# Resolver.net
KiCad netlist of a schematic drawn in Altium Designer
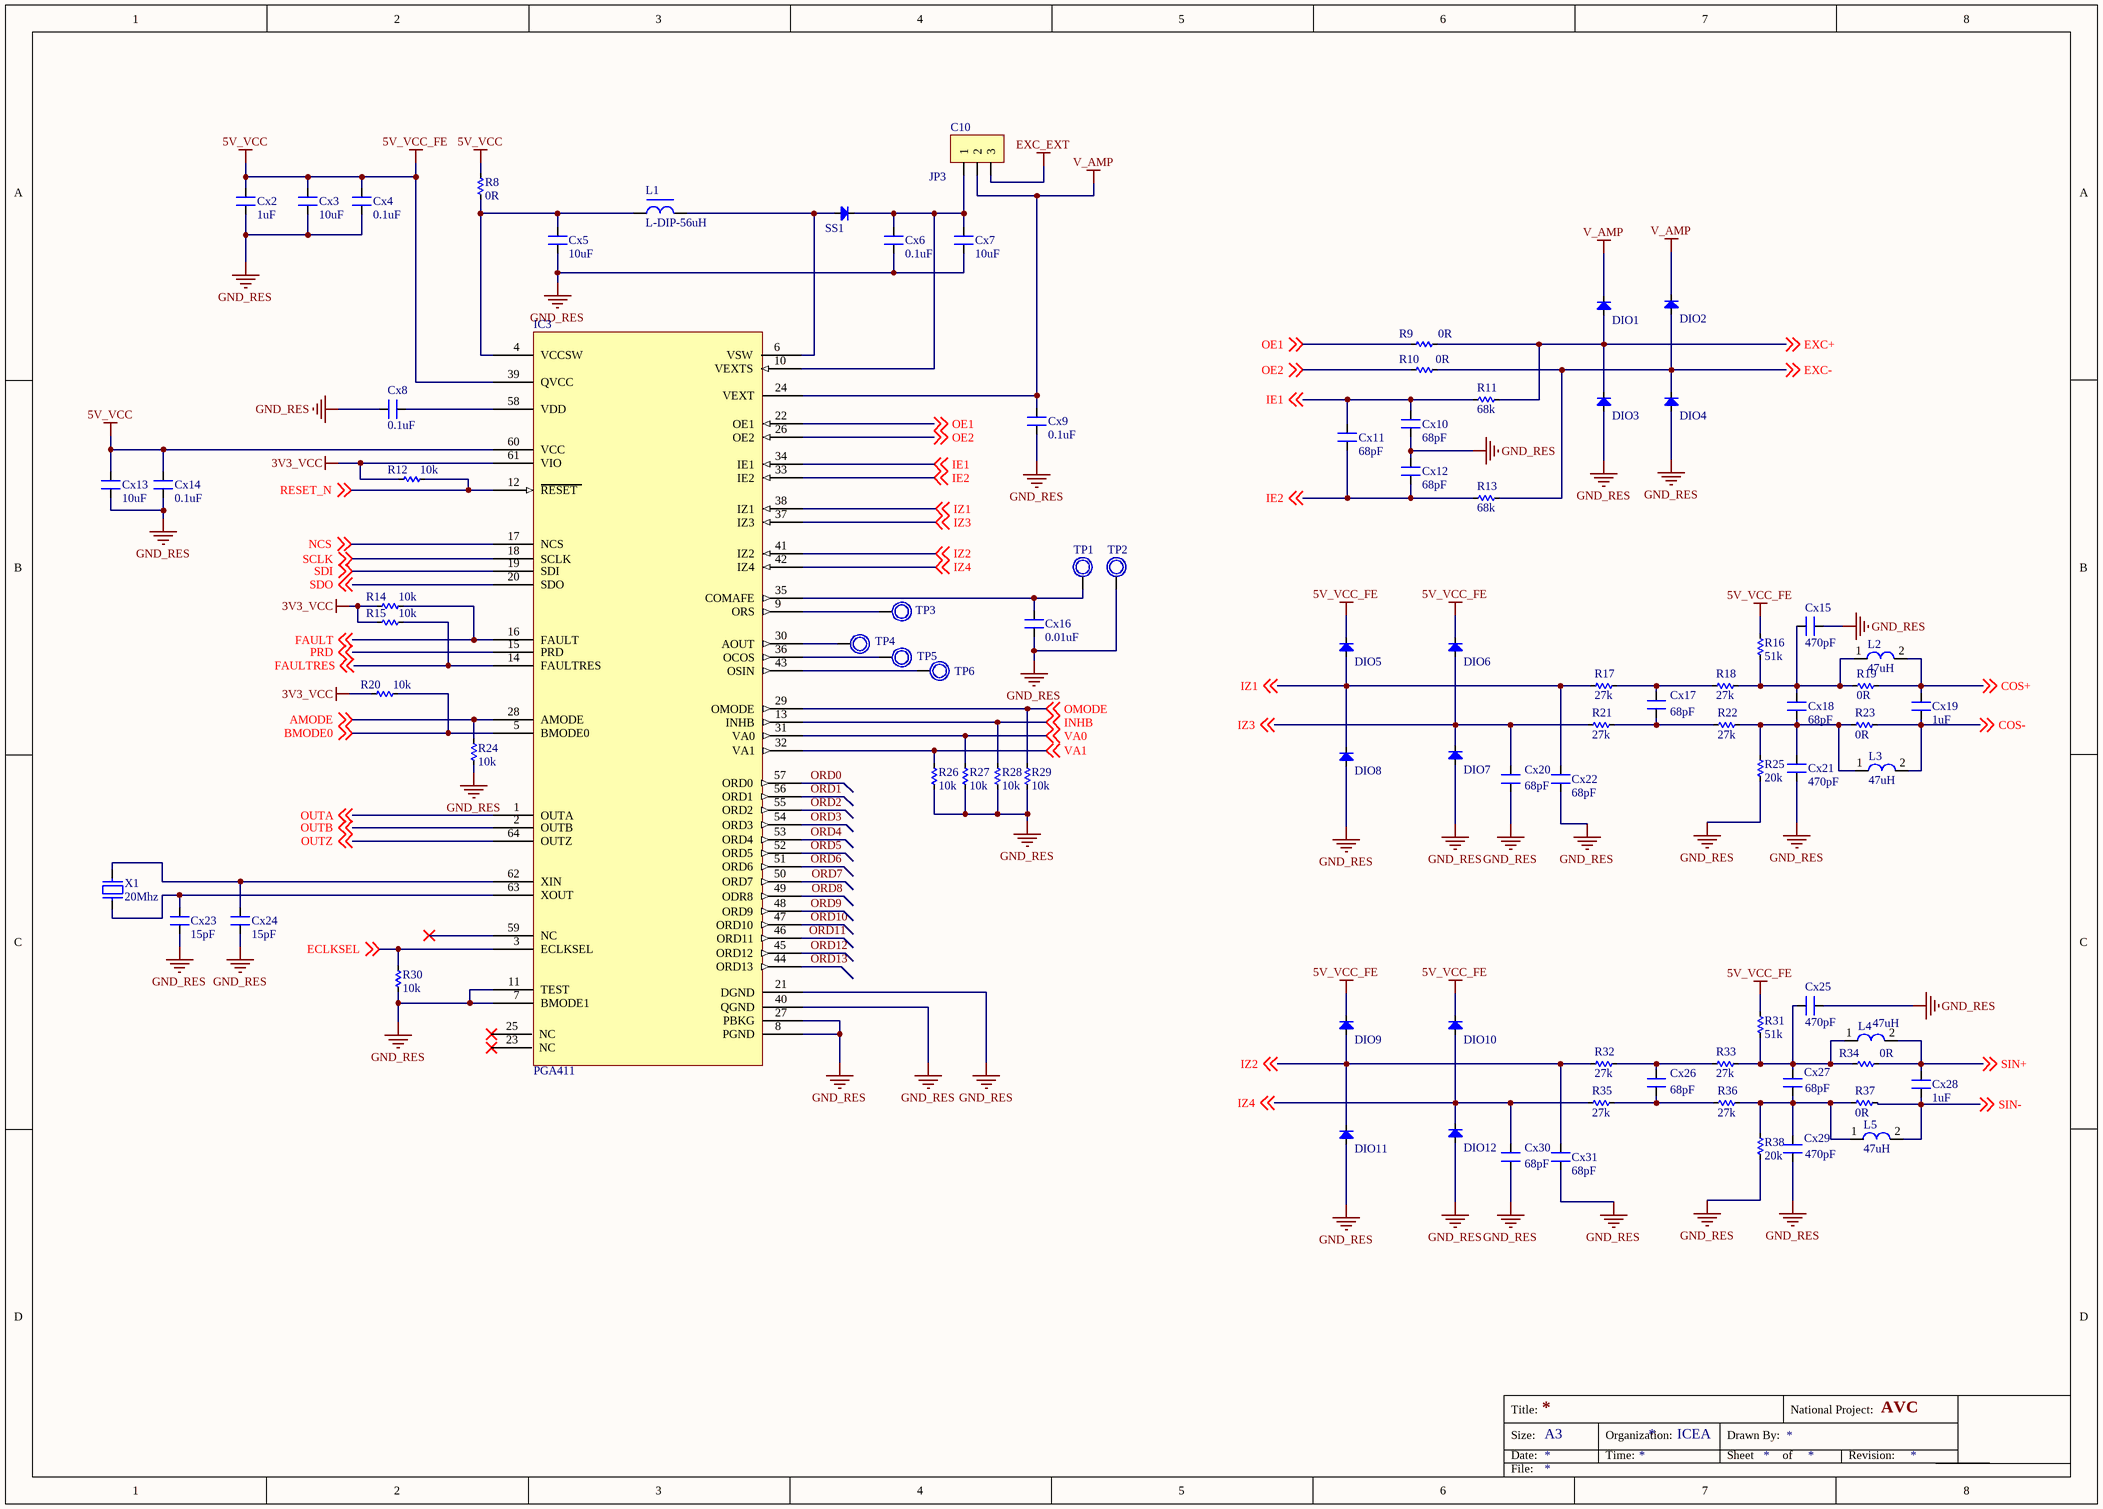
[diagram p0: Resolver.SchDoc]

(export (version "E")
  (design (tool "Eeschema 10.0.6"))
  (components
    (comp (ref "C10")
      (value "JP3")
      (footprint "JP3-CLOSED")
      (description "WR-PHD 2.54 mm Angled Socket Header")
      (fields
        (field (name "MANUFACTURER") "Würth Elektronik eiSos GmbH")
        (field (name "PARTNO") "613003143121")
        (field (name "CREATED BY") "Karrer Zheng")
      )
      (libsource (lib "ImetAltiumLibrary") (part "JP3"))
    )
    (comp (ref "Cx2")
      (value "1uF")
      (footprint "CN-SMD-0805")
      (libsource (lib "ImetAltiumLibrary") (part "CN"))
    )
    (comp (ref "Cx3")
      (value "10uF")
      (footprint "CN-SMD-1206")
      (libsource (lib "ImetAltiumLibrary") (part "CN"))
    )
    (comp (ref "Cx4")
      (value "0.1uF")
      (footprint "CN-SMD-0805")
      (libsource (lib "ImetAltiumLibrary") (part "CN"))
    )
    (comp (ref "Cx5")
      (value "10uF")
      (footprint "CN-SMD-1206")
      (libsource (lib "ImetAltiumLibrary") (part "CN"))
    )
    (comp (ref "Cx6")
      (value "0.1uF")
      (footprint "CN-SMD-0805")
      (libsource (lib "ImetAltiumLibrary") (part "CN"))
    )
    (comp (ref "Cx7")
      (value "10uF")
      (footprint "CN-SMD-1206")
      (libsource (lib "ImetAltiumLibrary") (part "CN"))
    )
    (comp (ref "Cx8")
      (value "0.1uF")
      (footprint "CN-SMD-0805")
      (libsource (lib "ImetAltiumLibrary") (part "CN"))
    )
    (comp (ref "Cx9")
      (value "0.1uF")
      (footprint "CN-SMD-0805")
      (libsource (lib "ImetAltiumLibrary") (part "CN"))
    )
    (comp (ref "Cx10")
      (value "68pF")
      (footprint "CN-SMD-0805")
      (libsource (lib "ImetAltiumLibrary") (part "CN"))
    )
    (comp (ref "Cx11")
      (value "68pF")
      (footprint "CN-SMD-0805")
      (libsource (lib "ImetAltiumLibrary") (part "CN"))
    )
    (comp (ref "Cx12")
      (value "68pF")
      (footprint "CN-SMD-0805")
      (libsource (lib "ImetAltiumLibrary") (part "CN"))
    )
    (comp (ref "Cx13")
      (value "10uF")
      (footprint "CN-SMD-1206")
      (libsource (lib "ImetAltiumLibrary") (part "CN"))
    )
    (comp (ref "Cx14")
      (value "0.1uF")
      (footprint "CN-SMD-0805")
      (libsource (lib "ImetAltiumLibrary") (part "CN"))
    )
    (comp (ref "Cx15")
      (value "470pF")
      (footprint "CN-SMD-0805")
      (libsource (lib "ImetAltiumLibrary") (part "CN"))
    )
    (comp (ref "Cx16")
      (value "0.01uF")
      (footprint "CN-SMD-0805")
      (libsource (lib "ImetAltiumLibrary") (part "CN"))
    )
    (comp (ref "Cx17")
      (value "68pF")
      (footprint "CN-SMD-0805")
      (libsource (lib "ImetAltiumLibrary") (part "CN"))
    )
    (comp (ref "Cx18")
      (value "68pF")
      (footprint "CN-SMD-0805")
      (libsource (lib "ImetAltiumLibrary") (part "CN"))
    )
    (comp (ref "Cx19")
      (value "1uF")
      (footprint "CN-SMD-0805")
      (libsource (lib "ImetAltiumLibrary") (part "CN"))
    )
    (comp (ref "Cx20")
      (value "68pF")
      (footprint "CN-SMD-0805")
      (libsource (lib "ImetAltiumLibrary") (part "CN"))
    )
    (comp (ref "Cx21")
      (value "470pF")
      (footprint "CN-SMD-0805")
      (libsource (lib "ImetAltiumLibrary") (part "CN"))
    )
    (comp (ref "Cx22")
      (value "68pF")
      (footprint "CN-SMD-0805")
      (libsource (lib "ImetAltiumLibrary") (part "CN"))
    )
    (comp (ref "Cx23")
      (value "15pF")
      (footprint "CN-SMD-0805")
      (libsource (lib "ImetAltiumLibrary") (part "CN"))
    )
    (comp (ref "Cx24")
      (value "15pF")
      (footprint "CN-SMD-0805")
      (libsource (lib "ImetAltiumLibrary") (part "CN"))
    )
    (comp (ref "Cx25")
      (value "470pF")
      (footprint "CN-SMD-0805")
      (libsource (lib "ImetAltiumLibrary") (part "CN"))
    )
    (comp (ref "Cx26")
      (value "68pF")
      (footprint "CN-SMD-0805")
      (libsource (lib "ImetAltiumLibrary") (part "CN"))
    )
    (comp (ref "Cx27")
      (value "68pF")
      (footprint "CN-SMD-0805")
      (libsource (lib "ImetAltiumLibrary") (part "CN"))
    )
    (comp (ref "Cx28")
      (value "1uF")
      (footprint "CN-SMD-0805")
      (libsource (lib "ImetAltiumLibrary") (part "CN"))
    )
    (comp (ref "Cx29")
      (value "470pF")
      (footprint "CN-SMD-0805")
      (libsource (lib "ImetAltiumLibrary") (part "CN"))
    )
    (comp (ref "Cx30")
      (value "68pF")
      (footprint "CN-SMD-0805")
      (libsource (lib "ImetAltiumLibrary") (part "CN"))
    )
    (comp (ref "Cx31")
      (value "68pF")
      (footprint "CN-SMD-0805")
      (libsource (lib "ImetAltiumLibrary") (part "CN"))
    )
    (comp (ref "DIO1")
      (value "Diode SMD")
      (footprint "DIO-SMD-106")
      (description "Default Diode")
      (fields (field (name "PUBLISHER") "Altium Limited"))
      (libsource (lib "ImetAltiumLibrary") (part "Diode SMD"))
    )
    (comp (ref "DIO2")
      (value "Diode SMD")
      (footprint "DIO-SMD-106")
      (description "Default Diode")
      (fields (field (name "PUBLISHER") "Altium Limited"))
      (libsource (lib "ImetAltiumLibrary") (part "Diode SMD"))
    )
    (comp (ref "DIO3")
      (value "Diode SMD")
      (footprint "DIO-SMD-106")
      (description "Default Diode")
      (fields (field (name "PUBLISHER") "Altium Limited"))
      (libsource (lib "ImetAltiumLibrary") (part "Diode SMD"))
    )
    (comp (ref "DIO4")
      (value "Diode SMD")
      (footprint "DIO-SMD-106")
      (description "Default Diode")
      (fields (field (name "PUBLISHER") "Altium Limited"))
      (libsource (lib "ImetAltiumLibrary") (part "Diode SMD"))
    )
    (comp (ref "DIO5")
      (value "Diode SMD")
      (footprint "DIO-SMD-106")
      (description "Default Diode")
      (fields (field (name "PUBLISHER") "Altium Limited"))
      (libsource (lib "ImetAltiumLibrary") (part "Diode SMD"))
    )
    (comp (ref "DIO6")
      (value "Diode SMD")
      (footprint "DIO-SMD-106")
      (description "Default Diode")
      (fields (field (name "PUBLISHER") "Altium Limited"))
      (libsource (lib "ImetAltiumLibrary") (part "Diode SMD"))
    )
    (comp (ref "DIO7")
      (value "Diode SMD")
      (footprint "DIO-SMD-106")
      (description "Default Diode")
      (fields (field (name "PUBLISHER") "Altium Limited"))
      (libsource (lib "ImetAltiumLibrary") (part "Diode SMD"))
    )
    (comp (ref "DIO8")
      (value "Diode SMD")
      (footprint "DIO-SMD-106")
      (description "Default Diode")
      (fields (field (name "PUBLISHER") "Altium Limited"))
      (libsource (lib "ImetAltiumLibrary") (part "Diode SMD"))
    )
    (comp (ref "DIO9")
      (value "Diode SMD")
      (footprint "DIO-SMD-106")
      (description "Default Diode")
      (fields (field (name "PUBLISHER") "Altium Limited"))
      (libsource (lib "ImetAltiumLibrary") (part "Diode SMD"))
    )
    (comp (ref "DIO10")
      (value "Diode SMD")
      (footprint "DIO-SMD-106")
      (description "Default Diode")
      (fields (field (name "PUBLISHER") "Altium Limited"))
      (libsource (lib "ImetAltiumLibrary") (part "Diode SMD"))
    )
    (comp (ref "DIO11")
      (value "Diode SMD")
      (footprint "DIO-SMD-106")
      (description "Default Diode")
      (fields (field (name "PUBLISHER") "Altium Limited"))
      (libsource (lib "ImetAltiumLibrary") (part "Diode SMD"))
    )
    (comp (ref "DIO12")
      (value "Diode SMD")
      (footprint "DIO-SMD-106")
      (description "Default Diode")
      (fields (field (name "PUBLISHER") "Altium Limited"))
      (libsource (lib "ImetAltiumLibrary") (part "Diode SMD"))
    )
    (comp (ref "IC3") (value "PGA411") (footprint "PGA411") (libsource (lib "PELAB") (part "PGA411")))
    (comp (ref "L1")
      (value "L-DIP-56uH")
      (footprint "L-DIP-M-13.5x6")
      (description "Inductor")
      (libsource (lib "ImetAltiumLibrary") (part "L-DIP-1"))
    )
    (comp (ref "L2")
      (value "47uH")
      (footprint "L CD43")
      (fields
        (field (name "PARTNO") "78477010")
        (field (name "MANUFACTURER") "Wurth Elektronik")
        (field (name "CREATED BY") "Baojun Chen")
      )
      (libsource (lib "ImetAltiumLibrary") (part "L-SMD-1"))
    )
    (comp (ref "L3")
      (value "47uH")
      (footprint "L CD43")
      (fields
        (field (name "PARTNO") "78477010")
        (field (name "MANUFACTURER") "Wurth Elektronik")
        (field (name "CREATED BY") "Baojun Chen")
      )
      (libsource (lib "ImetAltiumLibrary") (part "L-SMD-1"))
    )
    (comp (ref "L4")
      (value "47uH")
      (footprint "L CD43")
      (fields
        (field (name "PARTNO") "78477010")
        (field (name "MANUFACTURER") "Wurth Elektronik")
        (field (name "CREATED BY") "Baojun Chen")
      )
      (libsource (lib "ImetAltiumLibrary") (part "L-SMD-1"))
    )
    (comp (ref "L5")
      (value "47uH")
      (footprint "L CD43")
      (fields
        (field (name "PARTNO") "78477010")
        (field (name "MANUFACTURER") "Wurth Elektronik")
        (field (name "CREATED BY") "Baojun Chen")
      )
      (libsource (lib "ImetAltiumLibrary") (part "L-SMD-1"))
    )
    (comp (ref "R8")
      (value "0R")
      (footprint "RES-SMD-0805")
      (description "Resistor")
      (fields
        (field (name "MANUFACTURER") "Generic Components")
        (field (name "PUBLISHER") "Altium Hobart Technology Centre")
      )
      (libsource (lib "ImetAltiumLibrary") (part "Res-SMD"))
    )
    (comp (ref "R9")
      (value "0R")
      (footprint "RES-SMD-0805")
      (description "Resistor")
      (fields
        (field (name "MANUFACTURER") "Generic Components")
        (field (name "PUBLISHER") "Altium Hobart Technology Centre")
      )
      (libsource (lib "ImetAltiumLibrary") (part "Res-SMD"))
    )
    (comp (ref "R10")
      (value "0R")
      (footprint "RES-SMD-0805")
      (description "Resistor")
      (fields
        (field (name "MANUFACTURER") "Generic Components")
        (field (name "PUBLISHER") "Altium Hobart Technology Centre")
      )
      (libsource (lib "ImetAltiumLibrary") (part "Res-SMD"))
    )
    (comp (ref "R11")
      (value "68k")
      (footprint "RES-SMD-0805")
      (description "Resistor")
      (fields
        (field (name "MANUFACTURER") "Generic Components")
        (field (name "PUBLISHER") "Altium Hobart Technology Centre")
      )
      (libsource (lib "ImetAltiumLibrary") (part "Res-SMD"))
    )
    (comp (ref "R12")
      (value "10k")
      (footprint "RES-SMD-0805")
      (description "Resistor")
      (fields
        (field (name "MANUFACTURER") "Generic Components")
        (field (name "PUBLISHER") "Altium Hobart Technology Centre")
      )
      (libsource (lib "ImetAltiumLibrary") (part "Res-SMD"))
    )
    (comp (ref "R13")
      (value "68k")
      (footprint "RES-SMD-0805")
      (description "Resistor")
      (fields
        (field (name "MANUFACTURER") "Generic Components")
        (field (name "PUBLISHER") "Altium Hobart Technology Centre")
      )
      (libsource (lib "ImetAltiumLibrary") (part "Res-SMD"))
    )
    (comp (ref "R14")
      (value "10k")
      (footprint "RES-SMD-0805")
      (description "Resistor")
      (fields
        (field (name "MANUFACTURER") "Generic Components")
        (field (name "PUBLISHER") "Altium Hobart Technology Centre")
      )
      (libsource (lib "ImetAltiumLibrary") (part "Res-SMD"))
    )
    (comp (ref "R15")
      (value "10k")
      (footprint "RES-SMD-0805")
      (description "Resistor")
      (fields
        (field (name "MANUFACTURER") "Generic Components")
        (field (name "PUBLISHER") "Altium Hobart Technology Centre")
      )
      (libsource (lib "ImetAltiumLibrary") (part "Res-SMD"))
    )
    (comp (ref "R16")
      (value "51k")
      (footprint "RES-SMD-0805")
      (description "Resistor")
      (fields
        (field (name "MANUFACTURER") "Generic Components")
        (field (name "PUBLISHER") "Altium Hobart Technology Centre")
      )
      (libsource (lib "ImetAltiumLibrary") (part "Res-SMD"))
    )
    (comp (ref "R17")
      (value "27k")
      (footprint "RES-SMD-0805")
      (description "Resistor")
      (fields
        (field (name "MANUFACTURER") "Generic Components")
        (field (name "PUBLISHER") "Altium Hobart Technology Centre")
      )
      (libsource (lib "ImetAltiumLibrary") (part "Res-SMD"))
    )
    (comp (ref "R18")
      (value "27k")
      (footprint "RES-SMD-0805")
      (description "Resistor")
      (fields
        (field (name "MANUFACTURER") "Generic Components")
        (field (name "PUBLISHER") "Altium Hobart Technology Centre")
      )
      (libsource (lib "ImetAltiumLibrary") (part "Res-SMD"))
    )
    (comp (ref "R19")
      (value "0R")
      (footprint "RES-SMD-0805")
      (description "Resistor")
      (fields
        (field (name "MANUFACTURER") "Generic Components")
        (field (name "PUBLISHER") "Altium Hobart Technology Centre")
      )
      (libsource (lib "ImetAltiumLibrary") (part "Res-SMD"))
    )
    (comp (ref "R20")
      (value "10k")
      (footprint "RES-SMD-0805")
      (description "Resistor")
      (fields
        (field (name "MANUFACTURER") "Generic Components")
        (field (name "PUBLISHER") "Altium Hobart Technology Centre")
      )
      (libsource (lib "ImetAltiumLibrary") (part "Res-SMD"))
    )
    (comp (ref "R21")
      (value "27k")
      (footprint "RES-SMD-0805")
      (description "Resistor")
      (fields
        (field (name "MANUFACTURER") "Generic Components")
        (field (name "PUBLISHER") "Altium Hobart Technology Centre")
      )
      (libsource (lib "ImetAltiumLibrary") (part "Res-SMD"))
    )
    (comp (ref "R22")
      (value "27k")
      (footprint "RES-SMD-0805")
      (description "Resistor")
      (fields
        (field (name "MANUFACTURER") "Generic Components")
        (field (name "PUBLISHER") "Altium Hobart Technology Centre")
      )
      (libsource (lib "ImetAltiumLibrary") (part "Res-SMD"))
    )
    (comp (ref "R23")
      (value "0R")
      (footprint "RES-SMD-0805")
      (description "Resistor")
      (fields
        (field (name "MANUFACTURER") "Generic Components")
        (field (name "PUBLISHER") "Altium Hobart Technology Centre")
      )
      (libsource (lib "ImetAltiumLibrary") (part "Res-SMD"))
    )
    (comp (ref "R24")
      (value "10k")
      (footprint "RES-SMD-0805")
      (description "Resistor")
      (fields
        (field (name "MANUFACTURER") "Generic Components")
        (field (name "PUBLISHER") "Altium Hobart Technology Centre")
      )
      (libsource (lib "ImetAltiumLibrary") (part "Res-SMD"))
    )
    (comp (ref "R25")
      (value "20k")
      (footprint "RES-SMD-0805")
      (description "Resistor")
      (fields
        (field (name "MANUFACTURER") "Generic Components")
        (field (name "PUBLISHER") "Altium Hobart Technology Centre")
      )
      (libsource (lib "ImetAltiumLibrary") (part "Res-SMD"))
    )
    (comp (ref "R26")
      (value "10k")
      (footprint "RES-SMD-0805")
      (description "Resistor")
      (fields
        (field (name "MANUFACTURER") "Generic Components")
        (field (name "PUBLISHER") "Altium Hobart Technology Centre")
      )
      (libsource (lib "ImetAltiumLibrary") (part "Res-SMD"))
    )
    (comp (ref "R27")
      (value "10k")
      (footprint "RES-SMD-0805")
      (description "Resistor")
      (fields
        (field (name "MANUFACTURER") "Generic Components")
        (field (name "PUBLISHER") "Altium Hobart Technology Centre")
      )
      (libsource (lib "ImetAltiumLibrary") (part "Res-SMD"))
    )
    (comp (ref "R28")
      (value "10k")
      (footprint "RES-SMD-0805")
      (description "Resistor")
      (fields
        (field (name "MANUFACTURER") "Generic Components")
        (field (name "PUBLISHER") "Altium Hobart Technology Centre")
      )
      (libsource (lib "ImetAltiumLibrary") (part "Res-SMD"))
    )
    (comp (ref "R29")
      (value "10k")
      (footprint "RES-SMD-0805")
      (description "Resistor")
      (fields
        (field (name "MANUFACTURER") "Generic Components")
        (field (name "PUBLISHER") "Altium Hobart Technology Centre")
      )
      (libsource (lib "ImetAltiumLibrary") (part "Res-SMD"))
    )
    (comp (ref "R30")
      (value "10k")
      (footprint "RES-SMD-0805")
      (description "Resistor")
      (fields
        (field (name "MANUFACTURER") "Generic Components")
        (field (name "PUBLISHER") "Altium Hobart Technology Centre")
      )
      (libsource (lib "ImetAltiumLibrary") (part "Res-SMD"))
    )
    (comp (ref "R31")
      (value "51k")
      (footprint "RES-SMD-0805")
      (description "Resistor")
      (fields
        (field (name "MANUFACTURER") "Generic Components")
        (field (name "PUBLISHER") "Altium Hobart Technology Centre")
      )
      (libsource (lib "ImetAltiumLibrary") (part "Res-SMD"))
    )
    (comp (ref "R32")
      (value "27k")
      (footprint "RES-SMD-0805")
      (description "Resistor")
      (fields
        (field (name "MANUFACTURER") "Generic Components")
        (field (name "PUBLISHER") "Altium Hobart Technology Centre")
      )
      (libsource (lib "ImetAltiumLibrary") (part "Res-SMD"))
    )
    (comp (ref "R33")
      (value "27k")
      (footprint "RES-SMD-0805")
      (description "Resistor")
      (fields
        (field (name "MANUFACTURER") "Generic Components")
        (field (name "PUBLISHER") "Altium Hobart Technology Centre")
      )
      (libsource (lib "ImetAltiumLibrary") (part "Res-SMD"))
    )
    (comp (ref "R34")
      (value "0R")
      (footprint "RES-SMD-0805")
      (description "Resistor")
      (fields
        (field (name "MANUFACTURER") "Generic Components")
        (field (name "PUBLISHER") "Altium Hobart Technology Centre")
      )
      (libsource (lib "ImetAltiumLibrary") (part "Res-SMD"))
    )
    (comp (ref "R35")
      (value "27k")
      (footprint "RES-SMD-0805")
      (description "Resistor")
      (fields
        (field (name "MANUFACTURER") "Generic Components")
        (field (name "PUBLISHER") "Altium Hobart Technology Centre")
      )
      (libsource (lib "ImetAltiumLibrary") (part "Res-SMD"))
    )
    (comp (ref "R36")
      (value "27k")
      (footprint "RES-SMD-0805")
      (description "Resistor")
      (fields
        (field (name "MANUFACTURER") "Generic Components")
        (field (name "PUBLISHER") "Altium Hobart Technology Centre")
      )
      (libsource (lib "ImetAltiumLibrary") (part "Res-SMD"))
    )
    (comp (ref "R37")
      (value "0R")
      (footprint "RES-SMD-0805")
      (description "Resistor")
      (fields
        (field (name "MANUFACTURER") "Generic Components")
        (field (name "PUBLISHER") "Altium Hobart Technology Centre")
      )
      (libsource (lib "ImetAltiumLibrary") (part "Res-SMD"))
    )
    (comp (ref "R38")
      (value "20k")
      (footprint "RES-SMD-0805")
      (description "Resistor")
      (fields
        (field (name "MANUFACTURER") "Generic Components")
        (field (name "PUBLISHER") "Altium Hobart Technology Centre")
      )
      (libsource (lib "ImetAltiumLibrary") (part "Res-SMD"))
    )
    (comp (ref "SS1")
      (value "Diode SMD")
      (footprint "DIO-SMD-106")
      (description "Default Diode")
      (fields (field (name "PUBLISHER") "Altium Limited"))
      (libsource (lib "ImetAltiumLibrary") (part "Diode SMD"))
    )
    (comp (ref "TP1")
      (value "TP")
      (footprint "Test Point")
      (description "Test Point")
      (libsource (lib "") (part "TP1_1"))
    )
    (comp (ref "TP2")
      (value "TP")
      (footprint "Test Point")
      (description "Test Point")
      (libsource (lib "") (part "TP1_1"))
    )
    (comp (ref "TP3")
      (value "TP")
      (footprint "Test Point")
      (description "Test Point")
      (libsource (lib "PELAB") (part "TP1"))
    )
    (comp (ref "TP4")
      (value "TP")
      (footprint "Test Point")
      (description "Test Point")
      (libsource (lib "PELAB") (part "TP1"))
    )
    (comp (ref "TP5")
      (value "TP")
      (footprint "Test Point")
      (description "Test Point")
      (libsource (lib "PELAB") (part "TP1"))
    )
    (comp (ref "TP6")
      (value "TP")
      (footprint "Test Point")
      (description "Test Point")
      (libsource (lib "PELAB") (part "TP1"))
    )
    (comp (ref "X1")
      (value "20Mhz")
      (footprint "XT2 SMD")
      (description "Crystal, 32.768 KHz, -40 to 85 degC, 3.2 x 1.5 x 0.9 mm SMD")
      (libsource (lib "ImetAltiumLibrary") (part "XT2"))
    )
  )
  (nets
    (net (code "1") (name "/ORD0") (class "Default")
      (node (ref "IC3") (pin "57") (pinfunction "ORD0_57") (pintype "output"))
    )
    (net (code "2") (name "/ORD1") (class "Default")
      (node (ref "IC3") (pin "56") (pinfunction "ORD1_56") (pintype "output"))
    )
    (net (code "3") (name "/ORD2") (class "Default")
      (node (ref "IC3") (pin "55") (pinfunction "ORD2_55") (pintype "output"))
    )
    (net (code "4") (name "/ORD3") (class "Default")
      (node (ref "IC3") (pin "54") (pinfunction "ORD3_54") (pintype "output"))
    )
    (net (code "5") (name "/ORD4") (class "Default")
      (node (ref "IC3") (pin "53") (pinfunction "ORD4_53") (pintype "output"))
    )
    (net (code "6") (name "/ORD5") (class "Default")
      (node (ref "IC3") (pin "52") (pinfunction "ORD5_52") (pintype "output"))
    )
    (net (code "7") (name "/ORD6") (class "Default")
      (node (ref "IC3") (pin "51") (pinfunction "ORD6_51") (pintype "output"))
    )
    (net (code "8") (name "/ORD7") (class "Default")
      (node (ref "IC3") (pin "50") (pinfunction "ORD7_50") (pintype "output"))
    )
    (net (code "9") (name "/ORD8") (class "Default")
      (node (ref "IC3") (pin "49") (pinfunction "ODR8_49") (pintype "output"))
    )
    (net (code "10") (name "/ORD9") (class "Default")
      (node (ref "IC3") (pin "48") (pinfunction "ORD9_48") (pintype "output"))
    )
    (net (code "11") (name "/ORD10") (class "Default")
      (node (ref "IC3") (pin "47") (pinfunction "ORD10_47") (pintype "output"))
    )
    (net (code "12") (name "/ORD11") (class "Default")
      (node (ref "IC3") (pin "46") (pinfunction "ORD11_46") (pintype "output"))
    )
    (net (code "13") (name "/ORD12") (class "Default")
      (node (ref "IC3") (pin "45") (pinfunction "ORD12_45") (pintype "output"))
    )
    (net (code "14") (name "/ORD13") (class "Default")
      (node (ref "IC3") (pin "44") (pinfunction "ORD13_44") (pintype "output"))
    )
    (net (code "15") (name "3V3_VCC") (class "Default")
      (node (ref "IC3") (pin "61") (pinfunction "VIO_61") (pintype "passive"))
      (node (ref "R12") (pin "2") (pinfunction "2_2") (pintype "passive"))
      (node (ref "R14") (pin "2") (pinfunction "2_2") (pintype "passive"))
      (node (ref "R15") (pin "2") (pinfunction "2_2") (pintype "passive"))
      (node (ref "R20") (pin "2") (pinfunction "2_2") (pintype "passive"))
    )
    (net (code "16") (name "5V_VCC") (class "Default")
      (node (ref "Cx13") (pin "2") (pinfunction "2_2") (pintype "passive"))
      (node (ref "Cx14") (pin "2") (pinfunction "2_2") (pintype "passive"))
      (node (ref "Cx2") (pin "2") (pinfunction "2_2") (pintype "passive"))
      (node (ref "Cx3") (pin "2") (pinfunction "2_2") (pintype "passive"))
      (node (ref "Cx4") (pin "2") (pinfunction "2_2") (pintype "passive"))
      (node (ref "DIO10") (pin "2") (pinfunction "K_2") (pintype "passive"))
      (node (ref "DIO5") (pin "2") (pinfunction "K_2") (pintype "passive"))
      (node (ref "DIO6") (pin "2") (pinfunction "K_2") (pintype "passive"))
      (node (ref "DIO9") (pin "2") (pinfunction "K_2") (pintype "passive"))
      (node (ref "IC3") (pin "39") (pinfunction "QVCC_39") (pintype "passive"))
      (node (ref "IC3") (pin "60") (pinfunction "VCC_60") (pintype "passive"))
      (node (ref "R16") (pin "1") (pinfunction "1_1") (pintype "passive"))
      (node (ref "R31") (pin "1") (pinfunction "1_1") (pintype "passive"))
      (node (ref "R8") (pin "1") (pinfunction "1_1") (pintype "passive"))
    )
    (net (code "17") (name "AMODE") (class "Default")
      (node (ref "IC3") (pin "28") (pinfunction "AMODE_28") (pintype "passive"))
      (node (ref "R24") (pin "1") (pinfunction "1_1") (pintype "passive"))
    )
    (net (code "18") (name "BMODE0") (class "Default")
      (node (ref "IC3") (pin "5") (pinfunction "BMODE0_5") (pintype "passive"))
      (node (ref "R20") (pin "1") (pinfunction "1_1") (pintype "passive"))
    )
    (net (code "19") (name "COS+") (class "Default")
      (node (ref "Cx19") (pin "2") (pinfunction "2_2") (pintype "passive"))
      (node (ref "L2") (pin "2") (pinfunction "2_2") (pintype "passive"))
      (node (ref "R19") (pin "1") (pinfunction "1_1") (pintype "passive"))
    )
    (net (code "20") (name "COS-") (class "Default")
      (node (ref "Cx19") (pin "1") (pinfunction "1_1") (pintype "passive"))
      (node (ref "L3") (pin "2") (pinfunction "2_2") (pintype "passive"))
      (node (ref "R23") (pin "1") (pinfunction "1_1") (pintype "passive"))
    )
    (net (code "21") (name "ECLKSEL") (class "Default")
      (node (ref "IC3") (pin "3") (pinfunction "ECLKSEL_3") (pintype "passive"))
      (node (ref "R30") (pin "1") (pinfunction "1_1") (pintype "passive"))
    )
    (net (code "22") (name "EXC+") (class "Default")
      (node (ref "DIO1") (pin "1") (pinfunction "A_1") (pintype "passive"))
      (node (ref "DIO3") (pin "2") (pinfunction "K_2") (pintype "passive"))
      (node (ref "R11") (pin "1") (pinfunction "1_1") (pintype "passive"))
      (node (ref "R9") (pin "1") (pinfunction "1_1") (pintype "passive"))
    )
    (net (code "23") (name "EXC-") (class "Default")
      (node (ref "DIO2") (pin "1") (pinfunction "A_1") (pintype "passive"))
      (node (ref "DIO4") (pin "2") (pinfunction "K_2") (pintype "passive"))
      (node (ref "R10") (pin "1") (pinfunction "1_1") (pintype "passive"))
      (node (ref "R13") (pin "1") (pinfunction "1_1") (pintype "passive"))
    )
    (net (code "24") (name "EXC_EXT") (class "Default")
      (node (ref "C10") (pin "3") (pinfunction "3_3") (pintype "passive"))
    )
    (net (code "25") (name "FAULT") (class "Default")
      (node (ref "IC3") (pin "16") (pinfunction "FAULT_16") (pintype "passive"))
      (node (ref "R14") (pin "1") (pinfunction "1_1") (pintype "passive"))
    )
    (net (code "26") (name "FAULTRES") (class "Default")
      (node (ref "IC3") (pin "14") (pinfunction "FAULTRES_14") (pintype "passive"))
      (node (ref "R15") (pin "1") (pinfunction "1_1") (pintype "passive"))
    )
    (net (code "27") (name "GND_RES") (class "Default")
      (node (ref "Cx10") (pin "1") (pinfunction "1_1") (pintype "passive"))
      (node (ref "Cx12") (pin "2") (pinfunction "2_2") (pintype "passive"))
      (node (ref "Cx13") (pin "1") (pinfunction "1_1") (pintype "passive"))
      (node (ref "Cx14") (pin "1") (pinfunction "1_1") (pintype "passive"))
      (node (ref "Cx15") (pin "1") (pinfunction "1_1") (pintype "passive"))
      (node (ref "Cx16") (pin "1") (pinfunction "1_1") (pintype "passive"))
      (node (ref "Cx2") (pin "1") (pinfunction "1_1") (pintype "passive"))
      (node (ref "Cx20") (pin "1") (pinfunction "1_1") (pintype "passive"))
      (node (ref "Cx21") (pin "1") (pinfunction "1_1") (pintype "passive"))
      (node (ref "Cx22") (pin "2") (pinfunction "2_2") (pintype "passive"))
      (node (ref "Cx23") (pin "1") (pinfunction "1_1") (pintype "passive"))
      (node (ref "Cx24") (pin "1") (pinfunction "1_1") (pintype "passive"))
      (node (ref "Cx25") (pin "1") (pinfunction "1_1") (pintype "passive"))
      (node (ref "Cx29") (pin "1") (pinfunction "1_1") (pintype "passive"))
      (node (ref "Cx3") (pin "1") (pinfunction "1_1") (pintype "passive"))
      (node (ref "Cx30") (pin "1") (pinfunction "1_1") (pintype "passive"))
      (node (ref "Cx31") (pin "2") (pinfunction "2_2") (pintype "passive"))
      (node (ref "Cx4") (pin "1") (pinfunction "1_1") (pintype "passive"))
      (node (ref "Cx5") (pin "1") (pinfunction "1_1") (pintype "passive"))
      (node (ref "Cx6") (pin "1") (pinfunction "1_1") (pintype "passive"))
      (node (ref "Cx7") (pin "1") (pinfunction "1_1") (pintype "passive"))
      (node (ref "Cx8") (pin "2") (pinfunction "2_2") (pintype "passive"))
      (node (ref "Cx9") (pin "1") (pinfunction "1_1") (pintype "passive"))
      (node (ref "DIO11") (pin "1") (pinfunction "A_1") (pintype "passive"))
      (node (ref "DIO12") (pin "1") (pinfunction "A_1") (pintype "passive"))
      (node (ref "DIO3") (pin "1") (pinfunction "A_1") (pintype "passive"))
      (node (ref "DIO4") (pin "1") (pinfunction "A_1") (pintype "passive"))
      (node (ref "DIO7") (pin "1") (pinfunction "A_1") (pintype "passive"))
      (node (ref "DIO8") (pin "1") (pinfunction "A_1") (pintype "passive"))
      (node (ref "IC3") (pin "11") (pinfunction "TEST_11") (pintype "passive"))
      (node (ref "IC3") (pin "21") (pinfunction "DGND_21") (pintype "passive"))
      (node (ref "IC3") (pin "27") (pinfunction "PBKG_27") (pintype "passive"))
      (node (ref "IC3") (pin "40") (pinfunction "QGND_40") (pintype "passive"))
      (node (ref "IC3") (pin "7") (pinfunction "BMODE1_7") (pintype "passive"))
      (node (ref "IC3") (pin "8") (pinfunction "PGND_8") (pintype "passive"))
      (node (ref "R24") (pin "2") (pinfunction "2_2") (pintype "passive"))
      (node (ref "R25") (pin "2") (pinfunction "2_2") (pintype "passive"))
      (node (ref "R26") (pin "2") (pinfunction "2_2") (pintype "passive"))
      (node (ref "R27") (pin "2") (pinfunction "2_2") (pintype "passive"))
      (node (ref "R28") (pin "2") (pinfunction "2_2") (pintype "passive"))
      (node (ref "R29") (pin "2") (pinfunction "2_2") (pintype "passive"))
      (node (ref "R30") (pin "2") (pinfunction "2_2") (pintype "passive"))
      (node (ref "R38") (pin "2") (pinfunction "2_2") (pintype "passive"))
      (node (ref "TP2") (pin "1") (pinfunction "1_1") (pintype "passive"))
    )
    (net (code "28") (name "IE1") (class "Default")
      (node (ref "Cx10") (pin "2") (pinfunction "2_2") (pintype "passive"))
      (node (ref "Cx11") (pin "2") (pinfunction "2_2") (pintype "passive"))
      (node (ref "IC3") (pin "34") (pinfunction "IE1_34") (pintype "input"))
      (node (ref "R11") (pin "2") (pinfunction "2_2") (pintype "passive"))
    )
    (net (code "29") (name "IE2") (class "Default")
      (node (ref "Cx11") (pin "1") (pinfunction "1_1") (pintype "passive"))
      (node (ref "Cx12") (pin "1") (pinfunction "1_1") (pintype "passive"))
      (node (ref "IC3") (pin "33") (pinfunction "IE2_33") (pintype "input"))
      (node (ref "R13") (pin "2") (pinfunction "2_2") (pintype "passive"))
    )
    (net (code "30") (name "INHB") (class "Default")
      (node (ref "IC3") (pin "13") (pinfunction "INHB_13") (pintype "output"))
      (node (ref "R28") (pin "1") (pinfunction "1_1") (pintype "passive"))
    )
    (net (code "31") (name "IZ1") (class "Default")
      (node (ref "Cx22") (pin "1") (pinfunction "1_1") (pintype "passive"))
      (node (ref "DIO5") (pin "1") (pinfunction "A_1") (pintype "passive"))
      (node (ref "DIO8") (pin "2") (pinfunction "K_2") (pintype "passive"))
      (node (ref "IC3") (pin "38") (pinfunction "IZ1_38") (pintype "input"))
      (node (ref "R17") (pin "2") (pinfunction "2_2") (pintype "passive"))
    )
    (net (code "32") (name "IZ2") (class "Default")
      (node (ref "Cx31") (pin "1") (pinfunction "1_1") (pintype "passive"))
      (node (ref "DIO11") (pin "2") (pinfunction "K_2") (pintype "passive"))
      (node (ref "DIO9") (pin "1") (pinfunction "A_1") (pintype "passive"))
      (node (ref "IC3") (pin "41") (pinfunction "IZ2_41") (pintype "input"))
      (node (ref "R32") (pin "2") (pinfunction "2_2") (pintype "passive"))
    )
    (net (code "33") (name "IZ3") (class "Default")
      (node (ref "Cx20") (pin "2") (pinfunction "2_2") (pintype "passive"))
      (node (ref "DIO6") (pin "1") (pinfunction "A_1") (pintype "passive"))
      (node (ref "DIO7") (pin "2") (pinfunction "K_2") (pintype "passive"))
      (node (ref "IC3") (pin "37") (pinfunction "IZ3_37") (pintype "input"))
      (node (ref "R21") (pin "2") (pinfunction "2_2") (pintype "passive"))
    )
    (net (code "34") (name "IZ4") (class "Default")
      (node (ref "Cx30") (pin "2") (pinfunction "2_2") (pintype "passive"))
      (node (ref "DIO10") (pin "1") (pinfunction "A_1") (pintype "passive"))
      (node (ref "DIO12") (pin "2") (pinfunction "K_2") (pintype "passive"))
      (node (ref "IC3") (pin "42") (pinfunction "IZ4_42") (pintype "input"))
      (node (ref "R35") (pin "2") (pinfunction "2_2") (pintype "passive"))
    )
    (net (code "35") (name "NCS") (class "Default")
      (node (ref "IC3") (pin "17") (pinfunction "NCS_17") (pintype "passive"))
    )
    (net (code "36") (name "Net-(Cx15-Pad2)") (class "Default")
      (node (ref "Cx15") (pin "2") (pinfunction "2_2") (pintype "passive"))
      (node (ref "Cx18") (pin "2") (pinfunction "2_2") (pintype "passive"))
      (node (ref "L2") (pin "1") (pinfunction "1_1") (pintype "passive"))
      (node (ref "R16") (pin "2") (pinfunction "2_2") (pintype "passive"))
      (node (ref "R18") (pin "1") (pinfunction "1_1") (pintype "passive"))
      (node (ref "R19") (pin "2") (pinfunction "2_2") (pintype "passive"))
    )
    (net (code "37") (name "Net-(Cx17-Pad1)") (class "Default")
      (node (ref "Cx17") (pin "1") (pinfunction "1_1") (pintype "passive"))
      (node (ref "R21") (pin "1") (pinfunction "1_1") (pintype "passive"))
      (node (ref "R22") (pin "2") (pinfunction "2_2") (pintype "passive"))
    )
    (net (code "38") (name "Net-(Cx17-Pad2)") (class "Default")
      (node (ref "Cx17") (pin "2") (pinfunction "2_2") (pintype "passive"))
      (node (ref "R17") (pin "1") (pinfunction "1_1") (pintype "passive"))
      (node (ref "R18") (pin "2") (pinfunction "2_2") (pintype "passive"))
    )
    (net (code "39") (name "Net-(Cx18-Pad1)") (class "Default")
      (node (ref "Cx18") (pin "1") (pinfunction "1_1") (pintype "passive"))
      (node (ref "Cx21") (pin "2") (pinfunction "2_2") (pintype "passive"))
      (node (ref "L3") (pin "1") (pinfunction "1_1") (pintype "passive"))
      (node (ref "R22") (pin "1") (pinfunction "1_1") (pintype "passive"))
      (node (ref "R23") (pin "2") (pinfunction "2_2") (pintype "passive"))
      (node (ref "R25") (pin "1") (pinfunction "1_1") (pintype "passive"))
    )
    (net (code "40") (name "Net-(Cx25-Pad2)") (class "Default")
      (node (ref "Cx25") (pin "2") (pinfunction "2_2") (pintype "passive"))
      (node (ref "Cx27") (pin "2") (pinfunction "2_2") (pintype "passive"))
      (node (ref "L4") (pin "1") (pinfunction "1_1") (pintype "passive"))
      (node (ref "R31") (pin "2") (pinfunction "2_2") (pintype "passive"))
      (node (ref "R33") (pin "1") (pinfunction "1_1") (pintype "passive"))
      (node (ref "R34") (pin "2") (pinfunction "2_2") (pintype "passive"))
    )
    (net (code "41") (name "Net-(Cx26-Pad1)") (class "Default")
      (node (ref "Cx26") (pin "1") (pinfunction "1_1") (pintype "passive"))
      (node (ref "R35") (pin "1") (pinfunction "1_1") (pintype "passive"))
      (node (ref "R36") (pin "2") (pinfunction "2_2") (pintype "passive"))
    )
    (net (code "42") (name "Net-(Cx26-Pad2)") (class "Default")
      (node (ref "Cx26") (pin "2") (pinfunction "2_2") (pintype "passive"))
      (node (ref "R32") (pin "1") (pinfunction "1_1") (pintype "passive"))
      (node (ref "R33") (pin "2") (pinfunction "2_2") (pintype "passive"))
    )
    (net (code "43") (name "Net-(Cx27-Pad1)") (class "Default")
      (node (ref "Cx27") (pin "1") (pinfunction "1_1") (pintype "passive"))
      (node (ref "Cx29") (pin "2") (pinfunction "2_2") (pintype "passive"))
      (node (ref "L5") (pin "1") (pinfunction "1_1") (pintype "passive"))
      (node (ref "R36") (pin "1") (pinfunction "1_1") (pintype "passive"))
      (node (ref "R37") (pin "2") (pinfunction "2_2") (pintype "passive"))
      (node (ref "R38") (pin "1") (pinfunction "1_1") (pintype "passive"))
    )
    (net (code "44") (name "Net-(IC3-AOUT)") (class "Default")
      (node (ref "IC3") (pin "30") (pinfunction "AOUT_30") (pintype "output"))
      (node (ref "TP4") (pin "1") (pinfunction "1_1") (pintype "passive"))
    )
    (net (code "45") (name "Net-(IC3-COMAFE)") (class "Default")
      (node (ref "Cx16") (pin "2") (pinfunction "2_2") (pintype "passive"))
      (node (ref "IC3") (pin "35") (pinfunction "COMAFE_35") (pintype "output"))
      (node (ref "TP1") (pin "1") (pinfunction "1_1") (pintype "passive"))
    )
    (net (code "46") (name "Net-(IC3-OCOS)") (class "Default")
      (node (ref "IC3") (pin "36") (pinfunction "OCOS_36") (pintype "output"))
      (node (ref "TP5") (pin "1") (pinfunction "1_1") (pintype "passive"))
    )
    (net (code "47") (name "Net-(IC3-ORS)") (class "Default")
      (node (ref "IC3") (pin "9") (pinfunction "ORS_9") (pintype "output"))
      (node (ref "TP3") (pin "1") (pinfunction "1_1") (pintype "passive"))
    )
    (net (code "48") (name "Net-(IC3-OSIN)") (class "Default")
      (node (ref "IC3") (pin "43") (pinfunction "OSIN_43") (pintype "output"))
      (node (ref "TP6") (pin "1") (pinfunction "1_1") (pintype "passive"))
    )
    (net (code "49") (name "Net-(IC3-VCCSW)") (class "Default")
      (node (ref "Cx5") (pin "2") (pinfunction "2_2") (pintype "passive"))
      (node (ref "IC3") (pin "4") (pinfunction "VCCSW_4") (pintype "passive"))
      (node (ref "L1") (pin "1") (pinfunction "1_1") (pintype "passive"))
      (node (ref "R8") (pin "2") (pinfunction "2_2") (pintype "passive"))
    )
    (net (code "50") (name "Net-(IC3-VDD)") (class "Default")
      (node (ref "Cx8") (pin "1") (pinfunction "1_1") (pintype "passive"))
      (node (ref "IC3") (pin "58") (pinfunction "VDD_58") (pintype "passive"))
    )
    (net (code "51") (name "Net-(IC3-VEXTS)") (class "Default")
      (node (ref "C10") (pin "1") (pinfunction "1_1") (pintype "passive"))
      (node (ref "Cx6") (pin "2") (pinfunction "2_2") (pintype "passive"))
      (node (ref "Cx7") (pin "2") (pinfunction "2_2") (pintype "passive"))
      (node (ref "IC3") (pin "10") (pinfunction "VEXTS_10") (pintype "input"))
      (node (ref "SS1") (pin "2") (pinfunction "K_2") (pintype "passive"))
    )
    (net (code "52") (name "Net-(IC3-VSW)") (class "Default")
      (node (ref "IC3") (pin "6") (pinfunction "VSW_6") (pintype "passive"))
      (node (ref "L1") (pin "2") (pinfunction "2_2") (pintype "passive"))
      (node (ref "SS1") (pin "1") (pinfunction "A_1") (pintype "passive"))
    )
    (net (code "53") (name "Net-(IC3-XIN)") (class "Default")
      (node (ref "Cx24") (pin "2") (pinfunction "2_2") (pintype "passive"))
      (node (ref "IC3") (pin "62") (pinfunction "XIN_62") (pintype "passive"))
      (node (ref "X1") (pin "2") (pinfunction "2_2") (pintype "passive"))
    )
    (net (code "54") (name "Net-(IC3-XOUT)") (class "Default")
      (node (ref "Cx23") (pin "2") (pinfunction "2_2") (pintype "passive"))
      (node (ref "IC3") (pin "63") (pinfunction "XOUT_63") (pintype "passive"))
      (node (ref "X1") (pin "1") (pinfunction "1_1") (pintype "passive"))
    )
    (net (code "55") (name "OE1") (class "Default")
      (node (ref "IC3") (pin "22") (pinfunction "OE1_22") (pintype "input"))
      (node (ref "R9") (pin "2") (pinfunction "2_2") (pintype "passive"))
    )
    (net (code "56") (name "OE2") (class "Default")
      (node (ref "IC3") (pin "26") (pinfunction "OE2_26") (pintype "input"))
      (node (ref "R10") (pin "2") (pinfunction "2_2") (pintype "passive"))
    )
    (net (code "57") (name "OMODE") (class "Default")
      (node (ref "IC3") (pin "29") (pinfunction "OMODE_29") (pintype "output"))
      (node (ref "R29") (pin "1") (pinfunction "1_1") (pintype "passive"))
    )
    (net (code "58") (name "OUTA") (class "Default")
      (node (ref "IC3") (pin "1") (pinfunction "OUTA_1") (pintype "passive"))
    )
    (net (code "59") (name "OUTB") (class "Default")
      (node (ref "IC3") (pin "2") (pinfunction "OUTB_2") (pintype "passive"))
    )
    (net (code "60") (name "OUTZ") (class "Default")
      (node (ref "IC3") (pin "64") (pinfunction "OUTZ_64") (pintype "passive"))
    )
    (net (code "61") (name "PRD") (class "Default")
      (node (ref "IC3") (pin "15") (pinfunction "PRD_15") (pintype "passive"))
    )
    (net (code "62") (name "RESET_N") (class "Default")
      (node (ref "IC3") (pin "12") (pinfunction "RESET_12") (pintype "input"))
      (node (ref "R12") (pin "1") (pinfunction "1_1") (pintype "passive"))
    )
    (net (code "63") (name "SCLK") (class "Default")
      (node (ref "IC3") (pin "18") (pinfunction "SCLK_18") (pintype "passive"))
    )
    (net (code "64") (name "SDI") (class "Default")
      (node (ref "IC3") (pin "19") (pinfunction "SDI_19") (pintype "passive"))
    )
    (net (code "65") (name "SDO") (class "Default")
      (node (ref "IC3") (pin "20") (pinfunction "SDO_20") (pintype "passive"))
    )
    (net (code "66") (name "SIN+") (class "Default")
      (node (ref "Cx28") (pin "2") (pinfunction "2_2") (pintype "passive"))
      (node (ref "L4") (pin "2") (pinfunction "2_2") (pintype "passive"))
      (node (ref "R34") (pin "1") (pinfunction "1_1") (pintype "passive"))
    )
    (net (code "67") (name "SIN-") (class "Default")
      (node (ref "Cx28") (pin "1") (pinfunction "1_1") (pintype "passive"))
      (node (ref "L5") (pin "2") (pinfunction "2_2") (pintype "passive"))
      (node (ref "R37") (pin "1") (pinfunction "1_1") (pintype "passive"))
    )
    (net (code "68") (name "VA0") (class "Default")
      (node (ref "IC3") (pin "31") (pinfunction "VA0_31") (pintype "output"))
      (node (ref "R27") (pin "1") (pinfunction "1_1") (pintype "passive"))
    )
    (net (code "69") (name "VA1") (class "Default")
      (node (ref "IC3") (pin "32") (pinfunction "VA1_32") (pintype "output"))
      (node (ref "R26") (pin "1") (pinfunction "1_1") (pintype "passive"))
    )
    (net (code "70") (name "V_AMP") (class "Default")
      (node (ref "C10") (pin "2") (pinfunction "2_2") (pintype "passive"))
      (node (ref "Cx9") (pin "2") (pinfunction "2_2") (pintype "passive"))
      (node (ref "DIO1") (pin "2") (pinfunction "K_2") (pintype "passive"))
      (node (ref "DIO2") (pin "2") (pinfunction "K_2") (pintype "passive"))
      (node (ref "IC3") (pin "24") (pinfunction "VEXT_24") (pintype "passive"))
    )
    (net (code "71") (name "unconnected-(IC3-NC-Pad23)") (class "Default")
      (node (ref "IC3") (pin "23") (pinfunction "NC_23") (pintype "passive+no_connect"))
    )
    (net (code "72") (name "unconnected-(IC3-NC-Pad25)") (class "Default")
      (node (ref "IC3") (pin "25") (pinfunction "NC_25") (pintype "passive+no_connect"))
    )
    (net (code "73") (name "unconnected-(IC3-NC-Pad59)") (class "Default")
      (node (ref "IC3") (pin "59") (pinfunction "NC_59") (pintype "passive+no_connect"))
    )
  )
)
